# FAD8.net
KiCad netlist of a schematic drawn in EAGLE
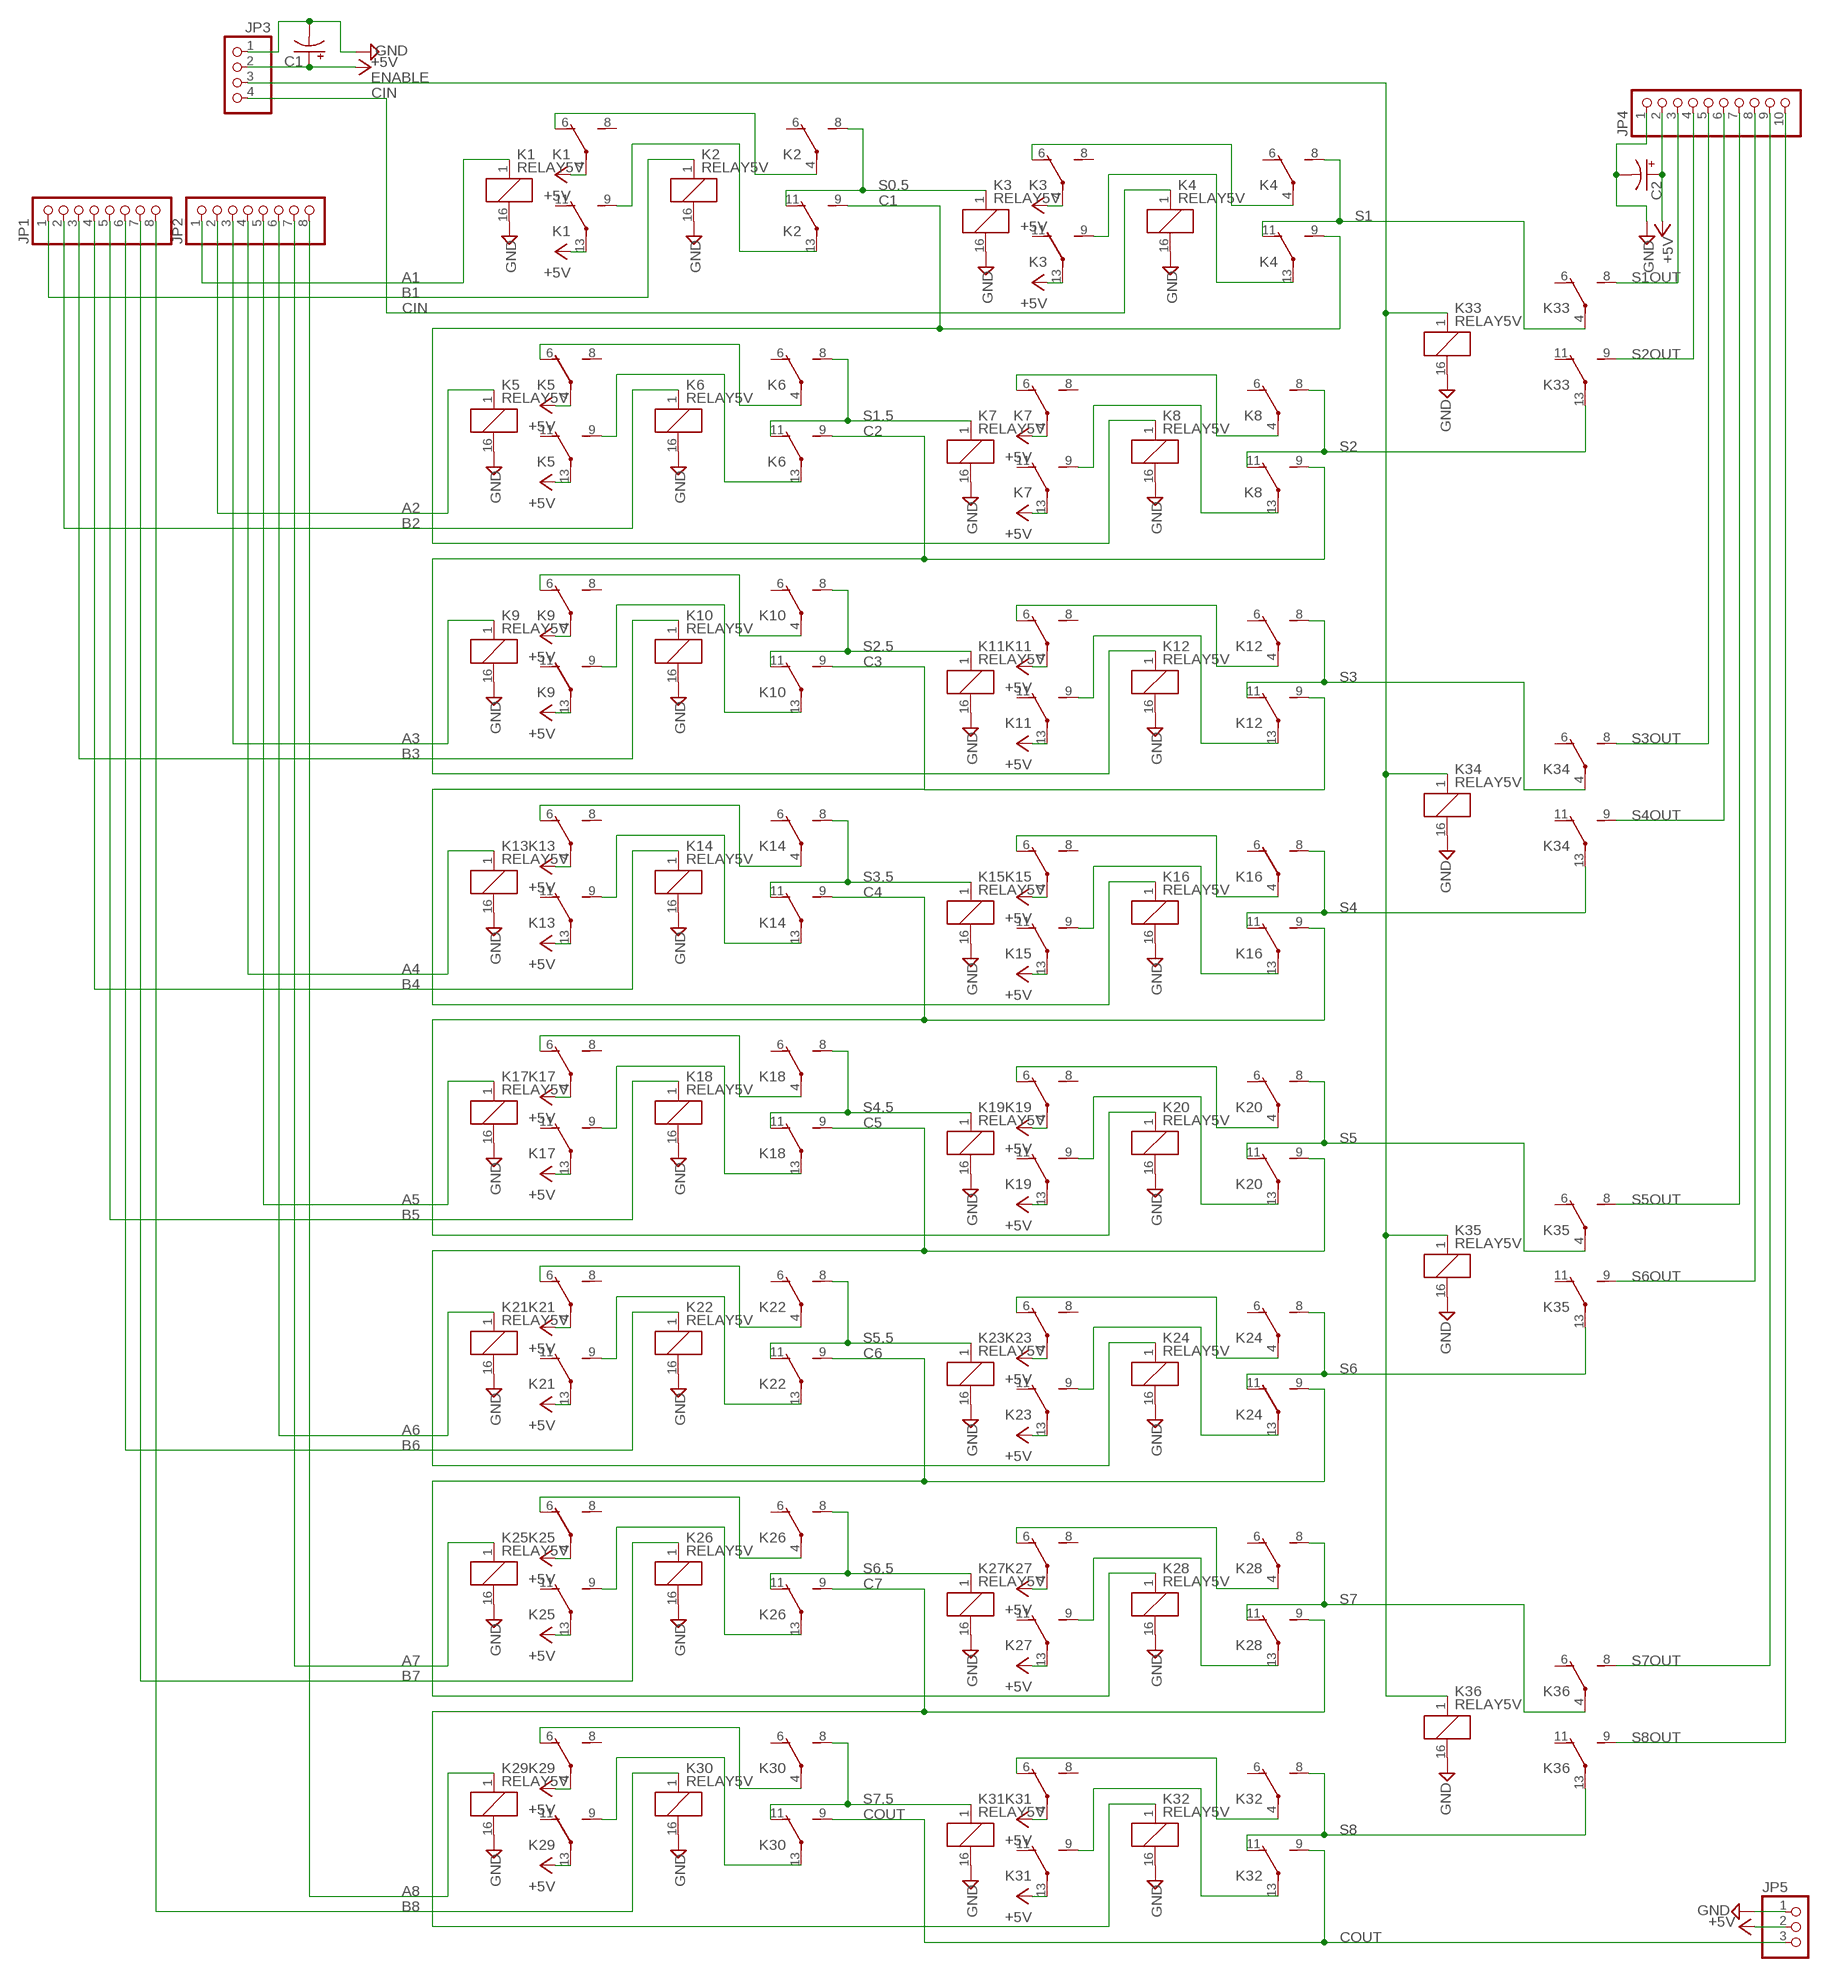
[diagram p0: schematic, sheet 1]

(export (version "E")
  (design (tool "Eeschema 10.0.6"))
  (components
    (comp (ref "C1")
      (value "CC-5-8.5")
      (footprint "eagle-import:E5-8,5")
      (libsource (lib "eagle-import") (part "CC-5-8.5"))
    )
    (comp (ref "C2")
      (value "CC-5-8.5")
      (footprint "eagle-import:E5-8,5")
      (libsource (lib "eagle-import") (part "CC-5-8.5"))
    )
    (comp (ref "JP1")
      (value "PINHD-1X8")
      (footprint "eagle-import:1X08")
      (libsource (lib "eagle-import") (part "PINHD-1X8"))
    )
    (comp (ref "JP2")
      (value "PINHD-1X8")
      (footprint "eagle-import:1X08")
      (libsource (lib "eagle-import") (part "PINHD-1X8"))
    )
    (comp (ref "JP3")
      (value "PINHD-1X4")
      (footprint "eagle-import:1X04")
      (libsource (lib "eagle-import") (part "PINHD-1X4"))
    )
    (comp (ref "JP4")
      (value "PINHD-1X10")
      (footprint "eagle-import:1X10")
      (libsource (lib "eagle-import") (part "PINHD-1X10"))
    )
    (comp (ref "JP5")
      (value "PINHD-1X3")
      (footprint "eagle-import:1X03")
      (libsource (lib "eagle-import") (part "PINHD-1X3"))
    )
    (comp (ref "K1")
      (value "RELAY5V")
      (footprint "eagle-import:DS-BT")
      (libsource (lib "eagle-import") (part "RELAY5V"))
    )
    (comp (ref "K2")
      (value "RELAY5V")
      (footprint "eagle-import:DS-BT")
      (libsource (lib "eagle-import") (part "RELAY5V"))
    )
    (comp (ref "K3")
      (value "RELAY5V")
      (footprint "eagle-import:DS-BT")
      (libsource (lib "eagle-import") (part "RELAY5V"))
    )
    (comp (ref "K4")
      (value "RELAY5V")
      (footprint "eagle-import:DS-BT")
      (libsource (lib "eagle-import") (part "RELAY5V"))
    )
    (comp (ref "K5")
      (value "RELAY5V")
      (footprint "eagle-import:DS-BT")
      (libsource (lib "eagle-import") (part "RELAY5V"))
    )
    (comp (ref "K6")
      (value "RELAY5V")
      (footprint "eagle-import:DS-BT")
      (libsource (lib "eagle-import") (part "RELAY5V"))
    )
    (comp (ref "K7")
      (value "RELAY5V")
      (footprint "eagle-import:DS-BT")
      (libsource (lib "eagle-import") (part "RELAY5V"))
    )
    (comp (ref "K8")
      (value "RELAY5V")
      (footprint "eagle-import:DS-BT")
      (libsource (lib "eagle-import") (part "RELAY5V"))
    )
    (comp (ref "K9")
      (value "RELAY5V")
      (footprint "eagle-import:DS-BT")
      (libsource (lib "eagle-import") (part "RELAY5V"))
    )
    (comp (ref "K10")
      (value "RELAY5V")
      (footprint "eagle-import:DS-BT")
      (libsource (lib "eagle-import") (part "RELAY5V"))
    )
    (comp (ref "K11")
      (value "RELAY5V")
      (footprint "eagle-import:DS-BT")
      (libsource (lib "eagle-import") (part "RELAY5V"))
    )
    (comp (ref "K12")
      (value "RELAY5V")
      (footprint "eagle-import:DS-BT")
      (libsource (lib "eagle-import") (part "RELAY5V"))
    )
    (comp (ref "K13")
      (value "RELAY5V")
      (footprint "eagle-import:DS-BT")
      (libsource (lib "eagle-import") (part "RELAY5V"))
    )
    (comp (ref "K14")
      (value "RELAY5V")
      (footprint "eagle-import:DS-BT")
      (libsource (lib "eagle-import") (part "RELAY5V"))
    )
    (comp (ref "K15")
      (value "RELAY5V")
      (footprint "eagle-import:DS-BT")
      (libsource (lib "eagle-import") (part "RELAY5V"))
    )
    (comp (ref "K16")
      (value "RELAY5V")
      (footprint "eagle-import:DS-BT")
      (libsource (lib "eagle-import") (part "RELAY5V"))
    )
    (comp (ref "K17")
      (value "RELAY5V")
      (footprint "eagle-import:DS-BT")
      (libsource (lib "eagle-import") (part "RELAY5V"))
    )
    (comp (ref "K18")
      (value "RELAY5V")
      (footprint "eagle-import:DS-BT")
      (libsource (lib "eagle-import") (part "RELAY5V"))
    )
    (comp (ref "K19")
      (value "RELAY5V")
      (footprint "eagle-import:DS-BT")
      (libsource (lib "eagle-import") (part "RELAY5V"))
    )
    (comp (ref "K20")
      (value "RELAY5V")
      (footprint "eagle-import:DS-BT")
      (libsource (lib "eagle-import") (part "RELAY5V"))
    )
    (comp (ref "K21")
      (value "RELAY5V")
      (footprint "eagle-import:DS-BT")
      (libsource (lib "eagle-import") (part "RELAY5V"))
    )
    (comp (ref "K22")
      (value "RELAY5V")
      (footprint "eagle-import:DS-BT")
      (libsource (lib "eagle-import") (part "RELAY5V"))
    )
    (comp (ref "K23")
      (value "RELAY5V")
      (footprint "eagle-import:DS-BT")
      (libsource (lib "eagle-import") (part "RELAY5V"))
    )
    (comp (ref "K24")
      (value "RELAY5V")
      (footprint "eagle-import:DS-BT")
      (libsource (lib "eagle-import") (part "RELAY5V"))
    )
    (comp (ref "K25")
      (value "RELAY5V")
      (footprint "eagle-import:DS-BT")
      (libsource (lib "eagle-import") (part "RELAY5V"))
    )
    (comp (ref "K26")
      (value "RELAY5V")
      (footprint "eagle-import:DS-BT")
      (libsource (lib "eagle-import") (part "RELAY5V"))
    )
    (comp (ref "K27")
      (value "RELAY5V")
      (footprint "eagle-import:DS-BT")
      (libsource (lib "eagle-import") (part "RELAY5V"))
    )
    (comp (ref "K28")
      (value "RELAY5V")
      (footprint "eagle-import:DS-BT")
      (libsource (lib "eagle-import") (part "RELAY5V"))
    )
    (comp (ref "K29")
      (value "RELAY5V")
      (footprint "eagle-import:DS-BT")
      (libsource (lib "eagle-import") (part "RELAY5V"))
    )
    (comp (ref "K30")
      (value "RELAY5V")
      (footprint "eagle-import:DS-BT")
      (libsource (lib "eagle-import") (part "RELAY5V"))
    )
    (comp (ref "K31")
      (value "RELAY5V")
      (footprint "eagle-import:DS-BT")
      (libsource (lib "eagle-import") (part "RELAY5V"))
    )
    (comp (ref "K32")
      (value "RELAY5V")
      (footprint "eagle-import:DS-BT")
      (libsource (lib "eagle-import") (part "RELAY5V"))
    )
    (comp (ref "K33")
      (value "RELAY5V")
      (footprint "eagle-import:DS-BT")
      (libsource (lib "eagle-import") (part "RELAY5V"))
    )
    (comp (ref "K34")
      (value "RELAY5V")
      (footprint "eagle-import:DS-BT")
      (libsource (lib "eagle-import") (part "RELAY5V"))
    )
    (comp (ref "K35")
      (value "RELAY5V")
      (footprint "eagle-import:DS-BT")
      (libsource (lib "eagle-import") (part "RELAY5V"))
    )
    (comp (ref "K36")
      (value "RELAY5V")
      (footprint "eagle-import:DS-BT")
      (libsource (lib "eagle-import") (part "RELAY5V"))
    )
  )
  (nets
    (net (code "1") (name "+5V") (class "Default")
      (node (ref "C1") (pin "+") (pinfunction "+_+") (pintype "passive"))
      (node (ref "C2") (pin "+") (pinfunction "+_+") (pintype "passive"))
      (node (ref "JP3") (pin "2") (pinfunction "2_2") (pintype "passive"))
      (node (ref "JP4") (pin "2") (pinfunction "2_2") (pintype "passive"))
      (node (ref "JP5") (pin "2") (pinfunction "2_2") (pintype "passive"))
      (node (ref "K1") (pin "13") (pinfunction "P_13") (pintype "passive"))
      (node (ref "K1") (pin "4") (pinfunction "P_4") (pintype "passive"))
      (node (ref "K11") (pin "13") (pinfunction "P_13") (pintype "passive"))
      (node (ref "K11") (pin "4") (pinfunction "P_4") (pintype "passive"))
      (node (ref "K13") (pin "13") (pinfunction "P_13") (pintype "passive"))
      (node (ref "K13") (pin "4") (pinfunction "P_4") (pintype "passive"))
      (node (ref "K15") (pin "13") (pinfunction "P_13") (pintype "passive"))
      (node (ref "K15") (pin "4") (pinfunction "P_4") (pintype "passive"))
      (node (ref "K17") (pin "13") (pinfunction "P_13") (pintype "passive"))
      (node (ref "K17") (pin "4") (pinfunction "P_4") (pintype "passive"))
      (node (ref "K19") (pin "13") (pinfunction "P_13") (pintype "passive"))
      (node (ref "K19") (pin "4") (pinfunction "P_4") (pintype "passive"))
      (node (ref "K21") (pin "13") (pinfunction "P_13") (pintype "passive"))
      (node (ref "K21") (pin "4") (pinfunction "P_4") (pintype "passive"))
      (node (ref "K23") (pin "13") (pinfunction "P_13") (pintype "passive"))
      (node (ref "K23") (pin "4") (pinfunction "P_4") (pintype "passive"))
      (node (ref "K25") (pin "13") (pinfunction "P_13") (pintype "passive"))
      (node (ref "K25") (pin "4") (pinfunction "P_4") (pintype "passive"))
      (node (ref "K27") (pin "13") (pinfunction "P_13") (pintype "passive"))
      (node (ref "K27") (pin "4") (pinfunction "P_4") (pintype "passive"))
      (node (ref "K29") (pin "13") (pinfunction "P_13") (pintype "passive"))
      (node (ref "K29") (pin "4") (pinfunction "P_4") (pintype "passive"))
      (node (ref "K3") (pin "13") (pinfunction "P_13") (pintype "passive"))
      (node (ref "K3") (pin "4") (pinfunction "P_4") (pintype "passive"))
      (node (ref "K31") (pin "13") (pinfunction "P_13") (pintype "passive"))
      (node (ref "K31") (pin "4") (pinfunction "P_4") (pintype "passive"))
      (node (ref "K5") (pin "13") (pinfunction "P_13") (pintype "passive"))
      (node (ref "K5") (pin "4") (pinfunction "P_4") (pintype "passive"))
      (node (ref "K7") (pin "13") (pinfunction "P_13") (pintype "passive"))
      (node (ref "K7") (pin "4") (pinfunction "P_4") (pintype "passive"))
      (node (ref "K9") (pin "13") (pinfunction "P_13") (pintype "passive"))
      (node (ref "K9") (pin "4") (pinfunction "P_4") (pintype "passive"))
    )
    (net (code "2") (name "/A1") (class "Default")
      (node (ref "JP2") (pin "1") (pinfunction "1_1") (pintype "passive"))
      (node (ref "K1") (pin "1") (pinfunction "+_1") (pintype "passive"))
    )
    (net (code "3") (name "/A2") (class "Default")
      (node (ref "JP2") (pin "2") (pinfunction "2_2") (pintype "passive"))
      (node (ref "K5") (pin "1") (pinfunction "+_1") (pintype "passive"))
    )
    (net (code "4") (name "/A3") (class "Default")
      (node (ref "JP2") (pin "3") (pinfunction "3_3") (pintype "passive"))
      (node (ref "K9") (pin "1") (pinfunction "+_1") (pintype "passive"))
    )
    (net (code "5") (name "/A4") (class "Default")
      (node (ref "JP2") (pin "4") (pinfunction "4_4") (pintype "passive"))
      (node (ref "K13") (pin "1") (pinfunction "+_1") (pintype "passive"))
    )
    (net (code "6") (name "/A5") (class "Default")
      (node (ref "JP2") (pin "5") (pinfunction "5_5") (pintype "passive"))
      (node (ref "K17") (pin "1") (pinfunction "+_1") (pintype "passive"))
    )
    (net (code "7") (name "/A6") (class "Default")
      (node (ref "JP2") (pin "6") (pinfunction "6_6") (pintype "passive"))
      (node (ref "K21") (pin "1") (pinfunction "+_1") (pintype "passive"))
    )
    (net (code "8") (name "/A7") (class "Default")
      (node (ref "JP2") (pin "7") (pinfunction "7_7") (pintype "passive"))
      (node (ref "K25") (pin "1") (pinfunction "+_1") (pintype "passive"))
    )
    (net (code "9") (name "/A8") (class "Default")
      (node (ref "JP2") (pin "8") (pinfunction "8_8") (pintype "passive"))
      (node (ref "K29") (pin "1") (pinfunction "+_1") (pintype "passive"))
    )
    (net (code "10") (name "/B1") (class "Default")
      (node (ref "JP1") (pin "1") (pinfunction "1_1") (pintype "passive"))
      (node (ref "K2") (pin "1") (pinfunction "+_1") (pintype "passive"))
    )
    (net (code "11") (name "/B2") (class "Default")
      (node (ref "JP1") (pin "2") (pinfunction "2_2") (pintype "passive"))
      (node (ref "K6") (pin "1") (pinfunction "+_1") (pintype "passive"))
    )
    (net (code "12") (name "/B3") (class "Default")
      (node (ref "JP1") (pin "3") (pinfunction "3_3") (pintype "passive"))
      (node (ref "K10") (pin "1") (pinfunction "+_1") (pintype "passive"))
    )
    (net (code "13") (name "/B4") (class "Default")
      (node (ref "JP1") (pin "4") (pinfunction "4_4") (pintype "passive"))
      (node (ref "K14") (pin "1") (pinfunction "+_1") (pintype "passive"))
    )
    (net (code "14") (name "/B5") (class "Default")
      (node (ref "JP1") (pin "5") (pinfunction "5_5") (pintype "passive"))
      (node (ref "K18") (pin "1") (pinfunction "+_1") (pintype "passive"))
    )
    (net (code "15") (name "/B6") (class "Default")
      (node (ref "JP1") (pin "6") (pinfunction "6_6") (pintype "passive"))
      (node (ref "K22") (pin "1") (pinfunction "+_1") (pintype "passive"))
    )
    (net (code "16") (name "/B7") (class "Default")
      (node (ref "JP1") (pin "7") (pinfunction "7_7") (pintype "passive"))
      (node (ref "K26") (pin "1") (pinfunction "+_1") (pintype "passive"))
    )
    (net (code "17") (name "/B8") (class "Default")
      (node (ref "JP1") (pin "8") (pinfunction "8_8") (pintype "passive"))
      (node (ref "K30") (pin "1") (pinfunction "+_1") (pintype "passive"))
    )
    (net (code "18") (name "/C1") (class "Default")
      (node (ref "K2") (pin "9") (pinfunction "S_9") (pintype "passive"))
      (node (ref "K4") (pin "9") (pinfunction "S_9") (pintype "passive"))
      (node (ref "K8") (pin "1") (pinfunction "+_1") (pintype "passive"))
    )
    (net (code "19") (name "/C2") (class "Default")
      (node (ref "K12") (pin "1") (pinfunction "+_1") (pintype "passive"))
      (node (ref "K6") (pin "9") (pinfunction "S_9") (pintype "passive"))
      (node (ref "K8") (pin "9") (pinfunction "S_9") (pintype "passive"))
    )
    (net (code "20") (name "/C3") (class "Default")
      (node (ref "K10") (pin "9") (pinfunction "S_9") (pintype "passive"))
      (node (ref "K12") (pin "9") (pinfunction "S_9") (pintype "passive"))
      (node (ref "K16") (pin "1") (pinfunction "+_1") (pintype "passive"))
    )
    (net (code "21") (name "/C4") (class "Default")
      (node (ref "K14") (pin "9") (pinfunction "S_9") (pintype "passive"))
      (node (ref "K16") (pin "9") (pinfunction "S_9") (pintype "passive"))
      (node (ref "K20") (pin "1") (pinfunction "+_1") (pintype "passive"))
    )
    (net (code "22") (name "/C5") (class "Default")
      (node (ref "K18") (pin "9") (pinfunction "S_9") (pintype "passive"))
      (node (ref "K20") (pin "9") (pinfunction "S_9") (pintype "passive"))
      (node (ref "K24") (pin "1") (pinfunction "+_1") (pintype "passive"))
    )
    (net (code "23") (name "/C6") (class "Default")
      (node (ref "K22") (pin "9") (pinfunction "S_9") (pintype "passive"))
      (node (ref "K24") (pin "9") (pinfunction "S_9") (pintype "passive"))
      (node (ref "K28") (pin "1") (pinfunction "+_1") (pintype "passive"))
    )
    (net (code "24") (name "/C7") (class "Default")
      (node (ref "K26") (pin "9") (pinfunction "S_9") (pintype "passive"))
      (node (ref "K28") (pin "9") (pinfunction "S_9") (pintype "passive"))
      (node (ref "K32") (pin "1") (pinfunction "+_1") (pintype "passive"))
    )
    (net (code "25") (name "/CIN") (class "Default")
      (node (ref "JP3") (pin "4") (pinfunction "4_4") (pintype "passive"))
      (node (ref "K4") (pin "1") (pinfunction "+_1") (pintype "passive"))
    )
    (net (code "26") (name "/COUT") (class "Default")
      (node (ref "JP5") (pin "3") (pinfunction "3_3") (pintype "passive"))
      (node (ref "K30") (pin "9") (pinfunction "S_9") (pintype "passive"))
      (node (ref "K32") (pin "9") (pinfunction "S_9") (pintype "passive"))
    )
    (net (code "27") (name "/ENABLE") (class "Default")
      (node (ref "JP3") (pin "3") (pinfunction "3_3") (pintype "passive"))
      (node (ref "K33") (pin "1") (pinfunction "+_1") (pintype "passive"))
      (node (ref "K34") (pin "1") (pinfunction "+_1") (pintype "passive"))
      (node (ref "K35") (pin "1") (pinfunction "+_1") (pintype "passive"))
      (node (ref "K36") (pin "1") (pinfunction "+_1") (pintype "passive"))
    )
    (net (code "28") (name "/S0.5") (class "Default")
      (node (ref "K2") (pin "11") (pinfunction "O_11") (pintype "passive"))
      (node (ref "K2") (pin "8") (pinfunction "S_8") (pintype "passive"))
      (node (ref "K3") (pin "1") (pinfunction "+_1") (pintype "passive"))
    )
    (net (code "29") (name "/S1") (class "Default")
      (node (ref "K33") (pin "4") (pinfunction "P_4") (pintype "passive"))
      (node (ref "K4") (pin "11") (pinfunction "O_11") (pintype "passive"))
      (node (ref "K4") (pin "8") (pinfunction "S_8") (pintype "passive"))
    )
    (net (code "30") (name "/S1.5") (class "Default")
      (node (ref "K6") (pin "11") (pinfunction "O_11") (pintype "passive"))
      (node (ref "K6") (pin "8") (pinfunction "S_8") (pintype "passive"))
      (node (ref "K7") (pin "1") (pinfunction "+_1") (pintype "passive"))
    )
    (net (code "31") (name "/S1OUT") (class "Default")
      (node (ref "JP4") (pin "3") (pinfunction "3_3") (pintype "passive"))
      (node (ref "K33") (pin "8") (pinfunction "S_8") (pintype "passive"))
    )
    (net (code "32") (name "/S2") (class "Default")
      (node (ref "K33") (pin "13") (pinfunction "P_13") (pintype "passive"))
      (node (ref "K8") (pin "11") (pinfunction "O_11") (pintype "passive"))
      (node (ref "K8") (pin "8") (pinfunction "S_8") (pintype "passive"))
    )
    (net (code "33") (name "/S2.5") (class "Default")
      (node (ref "K10") (pin "11") (pinfunction "O_11") (pintype "passive"))
      (node (ref "K10") (pin "8") (pinfunction "S_8") (pintype "passive"))
      (node (ref "K11") (pin "1") (pinfunction "+_1") (pintype "passive"))
    )
    (net (code "34") (name "/S2OUT") (class "Default")
      (node (ref "JP4") (pin "4") (pinfunction "4_4") (pintype "passive"))
      (node (ref "K33") (pin "9") (pinfunction "S_9") (pintype "passive"))
    )
    (net (code "35") (name "/S3") (class "Default")
      (node (ref "K12") (pin "11") (pinfunction "O_11") (pintype "passive"))
      (node (ref "K12") (pin "8") (pinfunction "S_8") (pintype "passive"))
      (node (ref "K34") (pin "4") (pinfunction "P_4") (pintype "passive"))
    )
    (net (code "36") (name "/S3.5") (class "Default")
      (node (ref "K14") (pin "11") (pinfunction "O_11") (pintype "passive"))
      (node (ref "K14") (pin "8") (pinfunction "S_8") (pintype "passive"))
      (node (ref "K15") (pin "1") (pinfunction "+_1") (pintype "passive"))
    )
    (net (code "37") (name "/S3OUT") (class "Default")
      (node (ref "JP4") (pin "5") (pinfunction "5_5") (pintype "passive"))
      (node (ref "K34") (pin "8") (pinfunction "S_8") (pintype "passive"))
    )
    (net (code "38") (name "/S4") (class "Default")
      (node (ref "K16") (pin "11") (pinfunction "O_11") (pintype "passive"))
      (node (ref "K16") (pin "8") (pinfunction "S_8") (pintype "passive"))
      (node (ref "K34") (pin "13") (pinfunction "P_13") (pintype "passive"))
    )
    (net (code "39") (name "/S4.5") (class "Default")
      (node (ref "K18") (pin "11") (pinfunction "O_11") (pintype "passive"))
      (node (ref "K18") (pin "8") (pinfunction "S_8") (pintype "passive"))
      (node (ref "K19") (pin "1") (pinfunction "+_1") (pintype "passive"))
    )
    (net (code "40") (name "/S4OUT") (class "Default")
      (node (ref "JP4") (pin "6") (pinfunction "6_6") (pintype "passive"))
      (node (ref "K34") (pin "9") (pinfunction "S_9") (pintype "passive"))
    )
    (net (code "41") (name "/S5") (class "Default")
      (node (ref "K20") (pin "11") (pinfunction "O_11") (pintype "passive"))
      (node (ref "K20") (pin "8") (pinfunction "S_8") (pintype "passive"))
      (node (ref "K35") (pin "4") (pinfunction "P_4") (pintype "passive"))
    )
    (net (code "42") (name "/S5.5") (class "Default")
      (node (ref "K22") (pin "11") (pinfunction "O_11") (pintype "passive"))
      (node (ref "K22") (pin "8") (pinfunction "S_8") (pintype "passive"))
      (node (ref "K23") (pin "1") (pinfunction "+_1") (pintype "passive"))
    )
    (net (code "43") (name "/S5OUT") (class "Default")
      (node (ref "JP4") (pin "7") (pinfunction "7_7") (pintype "passive"))
      (node (ref "K35") (pin "8") (pinfunction "S_8") (pintype "passive"))
    )
    (net (code "44") (name "/S6") (class "Default")
      (node (ref "K24") (pin "11") (pinfunction "O_11") (pintype "passive"))
      (node (ref "K24") (pin "8") (pinfunction "S_8") (pintype "passive"))
      (node (ref "K35") (pin "13") (pinfunction "P_13") (pintype "passive"))
    )
    (net (code "45") (name "/S6.5") (class "Default")
      (node (ref "K26") (pin "11") (pinfunction "O_11") (pintype "passive"))
      (node (ref "K26") (pin "8") (pinfunction "S_8") (pintype "passive"))
      (node (ref "K27") (pin "1") (pinfunction "+_1") (pintype "passive"))
    )
    (net (code "46") (name "/S6OUT") (class "Default")
      (node (ref "JP4") (pin "8") (pinfunction "8_8") (pintype "passive"))
      (node (ref "K35") (pin "9") (pinfunction "S_9") (pintype "passive"))
    )
    (net (code "47") (name "/S7") (class "Default")
      (node (ref "K28") (pin "11") (pinfunction "O_11") (pintype "passive"))
      (node (ref "K28") (pin "8") (pinfunction "S_8") (pintype "passive"))
      (node (ref "K36") (pin "4") (pinfunction "P_4") (pintype "passive"))
    )
    (net (code "48") (name "/S7.5") (class "Default")
      (node (ref "K30") (pin "11") (pinfunction "O_11") (pintype "passive"))
      (node (ref "K30") (pin "8") (pinfunction "S_8") (pintype "passive"))
      (node (ref "K31") (pin "1") (pinfunction "+_1") (pintype "passive"))
    )
    (net (code "49") (name "/S7OUT") (class "Default")
      (node (ref "JP4") (pin "9") (pinfunction "9_9") (pintype "passive"))
      (node (ref "K36") (pin "8") (pinfunction "S_8") (pintype "passive"))
    )
    (net (code "50") (name "/S8") (class "Default")
      (node (ref "K32") (pin "11") (pinfunction "O_11") (pintype "passive"))
      (node (ref "K32") (pin "8") (pinfunction "S_8") (pintype "passive"))
      (node (ref "K36") (pin "13") (pinfunction "P_13") (pintype "passive"))
    )
    (net (code "51") (name "/S8OUT") (class "Default")
      (node (ref "JP4") (pin "10") (pinfunction "10_10") (pintype "passive"))
      (node (ref "K36") (pin "9") (pinfunction "S_9") (pintype "passive"))
    )
    (net (code "52") (name "GND") (class "Default")
      (node (ref "C1") (pin "-") (pinfunction "-_-") (pintype "passive"))
      (node (ref "C2") (pin "-") (pinfunction "-_-") (pintype "passive"))
      (node (ref "JP3") (pin "1") (pinfunction "1_1") (pintype "passive"))
      (node (ref "JP4") (pin "1") (pinfunction "1_1") (pintype "passive"))
      (node (ref "JP5") (pin "1") (pinfunction "1_1") (pintype "passive"))
      (node (ref "K1") (pin "16") (pinfunction "-_16") (pintype "passive"))
      (node (ref "K10") (pin "16") (pinfunction "-_16") (pintype "passive"))
      (node (ref "K11") (pin "16") (pinfunction "-_16") (pintype "passive"))
      (node (ref "K12") (pin "16") (pinfunction "-_16") (pintype "passive"))
      (node (ref "K13") (pin "16") (pinfunction "-_16") (pintype "passive"))
      (node (ref "K14") (pin "16") (pinfunction "-_16") (pintype "passive"))
      (node (ref "K15") (pin "16") (pinfunction "-_16") (pintype "passive"))
      (node (ref "K16") (pin "16") (pinfunction "-_16") (pintype "passive"))
      (node (ref "K17") (pin "16") (pinfunction "-_16") (pintype "passive"))
      (node (ref "K18") (pin "16") (pinfunction "-_16") (pintype "passive"))
      (node (ref "K19") (pin "16") (pinfunction "-_16") (pintype "passive"))
      (node (ref "K2") (pin "16") (pinfunction "-_16") (pintype "passive"))
      (node (ref "K20") (pin "16") (pinfunction "-_16") (pintype "passive"))
      (node (ref "K21") (pin "16") (pinfunction "-_16") (pintype "passive"))
      (node (ref "K22") (pin "16") (pinfunction "-_16") (pintype "passive"))
      (node (ref "K23") (pin "16") (pinfunction "-_16") (pintype "passive"))
      (node (ref "K24") (pin "16") (pinfunction "-_16") (pintype "passive"))
      (node (ref "K25") (pin "16") (pinfunction "-_16") (pintype "passive"))
      (node (ref "K26") (pin "16") (pinfunction "-_16") (pintype "passive"))
      (node (ref "K27") (pin "16") (pinfunction "-_16") (pintype "passive"))
      (node (ref "K28") (pin "16") (pinfunction "-_16") (pintype "passive"))
      (node (ref "K29") (pin "16") (pinfunction "-_16") (pintype "passive"))
      (node (ref "K3") (pin "16") (pinfunction "-_16") (pintype "passive"))
      (node (ref "K30") (pin "16") (pinfunction "-_16") (pintype "passive"))
      (node (ref "K31") (pin "16") (pinfunction "-_16") (pintype "passive"))
      (node (ref "K32") (pin "16") (pinfunction "-_16") (pintype "passive"))
      (node (ref "K33") (pin "16") (pinfunction "-_16") (pintype "passive"))
      (node (ref "K34") (pin "16") (pinfunction "-_16") (pintype "passive"))
      (node (ref "K35") (pin "16") (pinfunction "-_16") (pintype "passive"))
      (node (ref "K36") (pin "16") (pinfunction "-_16") (pintype "passive"))
      (node (ref "K4") (pin "16") (pinfunction "-_16") (pintype "passive"))
      (node (ref "K5") (pin "16") (pinfunction "-_16") (pintype "passive"))
      (node (ref "K6") (pin "16") (pinfunction "-_16") (pintype "passive"))
      (node (ref "K7") (pin "16") (pinfunction "-_16") (pintype "passive"))
      (node (ref "K8") (pin "16") (pinfunction "-_16") (pintype "passive"))
      (node (ref "K9") (pin "16") (pinfunction "-_16") (pintype "passive"))
    )
    (net (code "53") (name "Net-(K1B-O)") (class "Default")
      (node (ref "K1") (pin "6") (pinfunction "O_6") (pintype "passive"))
      (node (ref "K2") (pin "4") (pinfunction "P_4") (pintype "passive"))
    )
    (net (code "54") (name "Net-(K1C-S)") (class "Default")
      (node (ref "K1") (pin "9") (pinfunction "S_9") (pintype "passive"))
      (node (ref "K2") (pin "13") (pinfunction "P_13") (pintype "passive"))
    )
    (net (code "55") (name "Net-(K3B-O)") (class "Default")
      (node (ref "K3") (pin "6") (pinfunction "O_6") (pintype "passive"))
      (node (ref "K4") (pin "4") (pinfunction "P_4") (pintype "passive"))
    )
    (net (code "56") (name "Net-(K3C-S)") (class "Default")
      (node (ref "K3") (pin "9") (pinfunction "S_9") (pintype "passive"))
      (node (ref "K4") (pin "13") (pinfunction "P_13") (pintype "passive"))
    )
    (net (code "57") (name "Net-(K5B-O)") (class "Default")
      (node (ref "K5") (pin "6") (pinfunction "O_6") (pintype "passive"))
      (node (ref "K6") (pin "4") (pinfunction "P_4") (pintype "passive"))
    )
    (net (code "58") (name "Net-(K5C-S)") (class "Default")
      (node (ref "K5") (pin "9") (pinfunction "S_9") (pintype "passive"))
      (node (ref "K6") (pin "13") (pinfunction "P_13") (pintype "passive"))
    )
    (net (code "59") (name "Net-(K7B-O)") (class "Default")
      (node (ref "K7") (pin "6") (pinfunction "O_6") (pintype "passive"))
      (node (ref "K8") (pin "4") (pinfunction "P_4") (pintype "passive"))
    )
    (net (code "60") (name "Net-(K7C-S)") (class "Default")
      (node (ref "K7") (pin "9") (pinfunction "S_9") (pintype "passive"))
      (node (ref "K8") (pin "13") (pinfunction "P_13") (pintype "passive"))
    )
    (net (code "61") (name "Net-(K10B-P)") (class "Default")
      (node (ref "K10") (pin "4") (pinfunction "P_4") (pintype "passive"))
      (node (ref "K9") (pin "6") (pinfunction "O_6") (pintype "passive"))
    )
    (net (code "62") (name "Net-(K10C-P)") (class "Default")
      (node (ref "K10") (pin "13") (pinfunction "P_13") (pintype "passive"))
      (node (ref "K9") (pin "9") (pinfunction "S_9") (pintype "passive"))
    )
    (net (code "63") (name "Net-(K11B-O)") (class "Default")
      (node (ref "K11") (pin "6") (pinfunction "O_6") (pintype "passive"))
      (node (ref "K12") (pin "4") (pinfunction "P_4") (pintype "passive"))
    )
    (net (code "64") (name "Net-(K11C-S)") (class "Default")
      (node (ref "K11") (pin "9") (pinfunction "S_9") (pintype "passive"))
      (node (ref "K12") (pin "13") (pinfunction "P_13") (pintype "passive"))
    )
    (net (code "65") (name "Net-(K13B-O)") (class "Default")
      (node (ref "K13") (pin "6") (pinfunction "O_6") (pintype "passive"))
      (node (ref "K14") (pin "4") (pinfunction "P_4") (pintype "passive"))
    )
    (net (code "66") (name "Net-(K13C-S)") (class "Default")
      (node (ref "K13") (pin "9") (pinfunction "S_9") (pintype "passive"))
      (node (ref "K14") (pin "13") (pinfunction "P_13") (pintype "passive"))
    )
    (net (code "67") (name "Net-(K15B-O)") (class "Default")
      (node (ref "K15") (pin "6") (pinfunction "O_6") (pintype "passive"))
      (node (ref "K16") (pin "4") (pinfunction "P_4") (pintype "passive"))
    )
    (net (code "68") (name "Net-(K15C-S)") (class "Default")
      (node (ref "K15") (pin "9") (pinfunction "S_9") (pintype "passive"))
      (node (ref "K16") (pin "13") (pinfunction "P_13") (pintype "passive"))
    )
    (net (code "69") (name "Net-(K17B-O)") (class "Default")
      (node (ref "K17") (pin "6") (pinfunction "O_6") (pintype "passive"))
      (node (ref "K18") (pin "4") (pinfunction "P_4") (pintype "passive"))
    )
    (net (code "70") (name "Net-(K17C-S)") (class "Default")
      (node (ref "K17") (pin "9") (pinfunction "S_9") (pintype "passive"))
      (node (ref "K18") (pin "13") (pinfunction "P_13") (pintype "passive"))
    )
    (net (code "71") (name "Net-(K19B-O)") (class "Default")
      (node (ref "K19") (pin "6") (pinfunction "O_6") (pintype "passive"))
      (node (ref "K20") (pin "4") (pinfunction "P_4") (pintype "passive"))
    )
    (net (code "72") (name "Net-(K19C-S)") (class "Default")
      (node (ref "K19") (pin "9") (pinfunction "S_9") (pintype "passive"))
      (node (ref "K20") (pin "13") (pinfunction "P_13") (pintype "passive"))
    )
    (net (code "73") (name "Net-(K21B-O)") (class "Default")
      (node (ref "K21") (pin "6") (pinfunction "O_6") (pintype "passive"))
      (node (ref "K22") (pin "4") (pinfunction "P_4") (pintype "passive"))
    )
    (net (code "74") (name "Net-(K21C-S)") (class "Default")
      (node (ref "K21") (pin "9") (pinfunction "S_9") (pintype "passive"))
      (node (ref "K22") (pin "13") (pinfunction "P_13") (pintype "passive"))
    )
    (net (code "75") (name "Net-(K23B-O)") (class "Default")
      (node (ref "K23") (pin "6") (pinfunction "O_6") (pintype "passive"))
      (node (ref "K24") (pin "4") (pinfunction "P_4") (pintype "passive"))
    )
    (net (code "76") (name "Net-(K23C-S)") (class "Default")
      (node (ref "K23") (pin "9") (pinfunction "S_9") (pintype "passive"))
      (node (ref "K24") (pin "13") (pinfunction "P_13") (pintype "passive"))
    )
    (net (code "77") (name "Net-(K25B-O)") (class "Default")
      (node (ref "K25") (pin "6") (pinfunction "O_6") (pintype "passive"))
      (node (ref "K26") (pin "4") (pinfunction "P_4") (pintype "passive"))
    )
    (net (code "78") (name "Net-(K25C-S)") (class "Default")
      (node (ref "K25") (pin "9") (pinfunction "S_9") (pintype "passive"))
      (node (ref "K26") (pin "13") (pinfunction "P_13") (pintype "passive"))
    )
    (net (code "79") (name "Net-(K27B-O)") (class "Default")
      (node (ref "K27") (pin "6") (pinfunction "O_6") (pintype "passive"))
      (node (ref "K28") (pin "4") (pinfunction "P_4") (pintype "passive"))
    )
    (net (code "80") (name "Net-(K27C-S)") (class "Default")
      (node (ref "K27") (pin "9") (pinfunction "S_9") (pintype "passive"))
      (node (ref "K28") (pin "13") (pinfunction "P_13") (pintype "passive"))
    )
    (net (code "81") (name "Net-(K29B-O)") (class "Default")
      (node (ref "K29") (pin "6") (pinfunction "O_6") (pintype "passive"))
      (node (ref "K30") (pin "4") (pinfunction "P_4") (pintype "passive"))
    )
    (net (code "82") (name "Net-(K29C-S)") (class "Default")
      (node (ref "K29") (pin "9") (pinfunction "S_9") (pintype "passive"))
      (node (ref "K30") (pin "13") (pinfunction "P_13") (pintype "passive"))
    )
    (net (code "83") (name "Net-(K31B-O)") (class "Default")
      (node (ref "K31") (pin "6") (pinfunction "O_6") (pintype "passive"))
      (node (ref "K32") (pin "4") (pinfunction "P_4") (pintype "passive"))
    )
    (net (code "84") (name "Net-(K31C-S)") (class "Default")
      (node (ref "K31") (pin "9") (pinfunction "S_9") (pintype "passive"))
      (node (ref "K32") (pin "13") (pinfunction "P_13") (pintype "passive"))
    )
    (net (code "85") (name "unconnected-(K1B-S-Pad8)") (class "Default")
      (node (ref "K1") (pin "8") (pinfunction "S_8") (pintype "passive"))
    )
    (net (code "86") (name "unconnected-(K1C-O-Pad11)") (class "Default")
      (node (ref "K1") (pin "11") (pinfunction "O_11") (pintype "passive"))
    )
    (net (code "87") (name "unconnected-(K2B-O-Pad6)") (class "Default")
      (node (ref "K2") (pin "6") (pinfunction "O_6") (pintype "passive"))
    )
    (net (code "88") (name "unconnected-(K3B-S-Pad8)") (class "Default")
      (node (ref "K3") (pin "8") (pinfunction "S_8") (pintype "passive"))
    )
    (net (code "89") (name "unconnected-(K3C-O-Pad11)") (class "Default")
      (node (ref "K3") (pin "11") (pinfunction "O_11") (pintype "passive"))
    )
    (net (code "90") (name "unconnected-(K4B-O-Pad6)") (class "Default")
      (node (ref "K4") (pin "6") (pinfunction "O_6") (pintype "passive"))
    )
    (net (code "91") (name "unconnected-(K5B-S-Pad8)") (class "Default")
      (node (ref "K5") (pin "8") (pinfunction "S_8") (pintype "passive"))
    )
    (net (code "92") (name "unconnected-(K5C-O-Pad11)") (class "Default")
      (node (ref "K5") (pin "11") (pinfunction "O_11") (pintype "passive"))
    )
    (net (code "93") (name "unconnected-(K6B-O-Pad6)") (class "Default")
      (node (ref "K6") (pin "6") (pinfunction "O_6") (pintype "passive"))
    )
    (net (code "94") (name "unconnected-(K7B-S-Pad8)") (class "Default")
      (node (ref "K7") (pin "8") (pinfunction "S_8") (pintype "passive"))
    )
    (net (code "95") (name "unconnected-(K7C-O-Pad11)") (class "Default")
      (node (ref "K7") (pin "11") (pinfunction "O_11") (pintype "passive"))
    )
    (net (code "96") (name "unconnected-(K8B-O-Pad6)") (class "Default")
      (node (ref "K8") (pin "6") (pinfunction "O_6") (pintype "passive"))
    )
    (net (code "97") (name "unconnected-(K9B-S-Pad8)") (class "Default")
      (node (ref "K9") (pin "8") (pinfunction "S_8") (pintype "passive"))
    )
    (net (code "98") (name "unconnected-(K9C-O-Pad11)") (class "Default")
      (node (ref "K9") (pin "11") (pinfunction "O_11") (pintype "passive"))
    )
    (net (code "99") (name "unconnected-(K10B-O-Pad6)") (class "Default")
      (node (ref "K10") (pin "6") (pinfunction "O_6") (pintype "passive"))
    )
    (net (code "100") (name "unconnected-(K11B-S-Pad8)") (class "Default")
      (node (ref "K11") (pin "8") (pinfunction "S_8") (pintype "passive"))
    )
    (net (code "101") (name "unconnected-(K11C-O-Pad11)") (class "Default")
      (node (ref "K11") (pin "11") (pinfunction "O_11") (pintype "passive"))
    )
    (net (code "102") (name "unconnected-(K12B-O-Pad6)") (class "Default")
      (node (ref "K12") (pin "6") (pinfunction "O_6") (pintype "passive"))
    )
    (net (code "103") (name "unconnected-(K13B-S-Pad8)") (class "Default")
      (node (ref "K13") (pin "8") (pinfunction "S_8") (pintype "passive"))
    )
    (net (code "104") (name "unconnected-(K13C-O-Pad11)") (class "Default")
      (node (ref "K13") (pin "11") (pinfunction "O_11") (pintype "passive"))
    )
    (net (code "105") (name "unconnected-(K14B-O-Pad6)") (class "Default")
      (node (ref "K14") (pin "6") (pinfunction "O_6") (pintype "passive"))
    )
    (net (code "106") (name "unconnected-(K15B-S-Pad8)") (class "Default")
      (node (ref "K15") (pin "8") (pinfunction "S_8") (pintype "passive"))
    )
    (net (code "107") (name "unconnected-(K15C-O-Pad11)") (class "Default")
      (node (ref "K15") (pin "11") (pinfunction "O_11") (pintype "passive"))
    )
    (net (code "108") (name "unconnected-(K16B-O-Pad6)") (class "Default")
      (node (ref "K16") (pin "6") (pinfunction "O_6") (pintype "passive"))
    )
    (net (code "109") (name "unconnected-(K17B-S-Pad8)") (class "Default")
      (node (ref "K17") (pin "8") (pinfunction "S_8") (pintype "passive"))
    )
    (net (code "110") (name "unconnected-(K17C-O-Pad11)") (class "Default")
      (node (ref "K17") (pin "11") (pinfunction "O_11") (pintype "passive"))
    )
    (net (code "111") (name "unconnected-(K18B-O-Pad6)") (class "Default")
      (node (ref "K18") (pin "6") (pinfunction "O_6") (pintype "passive"))
    )
    (net (code "112") (name "unconnected-(K19B-S-Pad8)") (class "Default")
      (node (ref "K19") (pin "8") (pinfunction "S_8") (pintype "passive"))
    )
    (net (code "113") (name "unconnected-(K19C-O-Pad11)") (class "Default")
      (node (ref "K19") (pin "11") (pinfunction "O_11") (pintype "passive"))
    )
    (net (code "114") (name "unconnected-(K20B-O-Pad6)") (class "Default")
      (node (ref "K20") (pin "6") (pinfunction "O_6") (pintype "passive"))
    )
    (net (code "115") (name "unconnected-(K21B-S-Pad8)") (class "Default")
      (node (ref "K21") (pin "8") (pinfunction "S_8") (pintype "passive"))
    )
    (net (code "116") (name "unconnected-(K21C-O-Pad11)") (class "Default")
      (node (ref "K21") (pin "11") (pinfunction "O_11") (pintype "passive"))
    )
    (net (code "117") (name "unconnected-(K22B-O-Pad6)") (class "Default")
      (node (ref "K22") (pin "6") (pinfunction "O_6") (pintype "passive"))
    )
    (net (code "118") (name "unconnected-(K23B-S-Pad8)") (class "Default")
      (node (ref "K23") (pin "8") (pinfunction "S_8") (pintype "passive"))
    )
    (net (code "119") (name "unconnected-(K23C-O-Pad11)") (class "Default")
      (node (ref "K23") (pin "11") (pinfunction "O_11") (pintype "passive"))
    )
    (net (code "120") (name "unconnected-(K24B-O-Pad6)") (class "Default")
      (node (ref "K24") (pin "6") (pinfunction "O_6") (pintype "passive"))
    )
    (net (code "121") (name "unconnected-(K25B-S-Pad8)") (class "Default")
      (node (ref "K25") (pin "8") (pinfunction "S_8") (pintype "passive"))
    )
    (net (code "122") (name "unconnected-(K25C-O-Pad11)") (class "Default")
      (node (ref "K25") (pin "11") (pinfunction "O_11") (pintype "passive"))
    )
    (net (code "123") (name "unconnected-(K26B-O-Pad6)") (class "Default")
      (node (ref "K26") (pin "6") (pinfunction "O_6") (pintype "passive"))
    )
    (net (code "124") (name "unconnected-(K27B-S-Pad8)") (class "Default")
      (node (ref "K27") (pin "8") (pinfunction "S_8") (pintype "passive"))
    )
    (net (code "125") (name "unconnected-(K27C-O-Pad11)") (class "Default")
      (node (ref "K27") (pin "11") (pinfunction "O_11") (pintype "passive"))
    )
    (net (code "126") (name "unconnected-(K28B-O-Pad6)") (class "Default")
      (node (ref "K28") (pin "6") (pinfunction "O_6") (pintype "passive"))
    )
    (net (code "127") (name "unconnected-(K29B-S-Pad8)") (class "Default")
      (node (ref "K29") (pin "8") (pinfunction "S_8") (pintype "passive"))
    )
    (net (code "128") (name "unconnected-(K29C-O-Pad11)") (class "Default")
      (node (ref "K29") (pin "11") (pinfunction "O_11") (pintype "passive"))
    )
    (net (code "129") (name "unconnected-(K30B-O-Pad6)") (class "Default")
      (node (ref "K30") (pin "6") (pinfunction "O_6") (pintype "passive"))
    )
    (net (code "130") (name "unconnected-(K31B-S-Pad8)") (class "Default")
      (node (ref "K31") (pin "8") (pinfunction "S_8") (pintype "passive"))
    )
    (net (code "131") (name "unconnected-(K31C-O-Pad11)") (class "Default")
      (node (ref "K31") (pin "11") (pinfunction "O_11") (pintype "passive"))
    )
    (net (code "132") (name "unconnected-(K32B-O-Pad6)") (class "Default")
      (node (ref "K32") (pin "6") (pinfunction "O_6") (pintype "passive"))
    )
    (net (code "133") (name "unconnected-(K33B-O-Pad6)") (class "Default")
      (node (ref "K33") (pin "6") (pinfunction "O_6") (pintype "passive"))
    )
    (net (code "134") (name "unconnected-(K33C-O-Pad11)") (class "Default")
      (node (ref "K33") (pin "11") (pinfunction "O_11") (pintype "passive"))
    )
    (net (code "135") (name "unconnected-(K34B-O-Pad6)") (class "Default")
      (node (ref "K34") (pin "6") (pinfunction "O_6") (pintype "passive"))
    )
    (net (code "136") (name "unconnected-(K34C-O-Pad11)") (class "Default")
      (node (ref "K34") (pin "11") (pinfunction "O_11") (pintype "passive"))
    )
    (net (code "137") (name "unconnected-(K35B-O-Pad6)") (class "Default")
      (node (ref "K35") (pin "6") (pinfunction "O_6") (pintype "passive"))
    )
    (net (code "138") (name "unconnected-(K35C-O-Pad11)") (class "Default")
      (node (ref "K35") (pin "11") (pinfunction "O_11") (pintype "passive"))
    )
    (net (code "139") (name "unconnected-(K36B-O-Pad6)") (class "Default")
      (node (ref "K36") (pin "6") (pinfunction "O_6") (pintype "passive"))
    )
    (net (code "140") (name "unconnected-(K36C-O-Pad11)") (class "Default")
      (node (ref "K36") (pin "11") (pinfunction "O_11") (pintype "passive"))
    )
  )
)
